# 11_EXPANSION_CN.net
KiCad netlist of a schematic drawn in Altium Designer
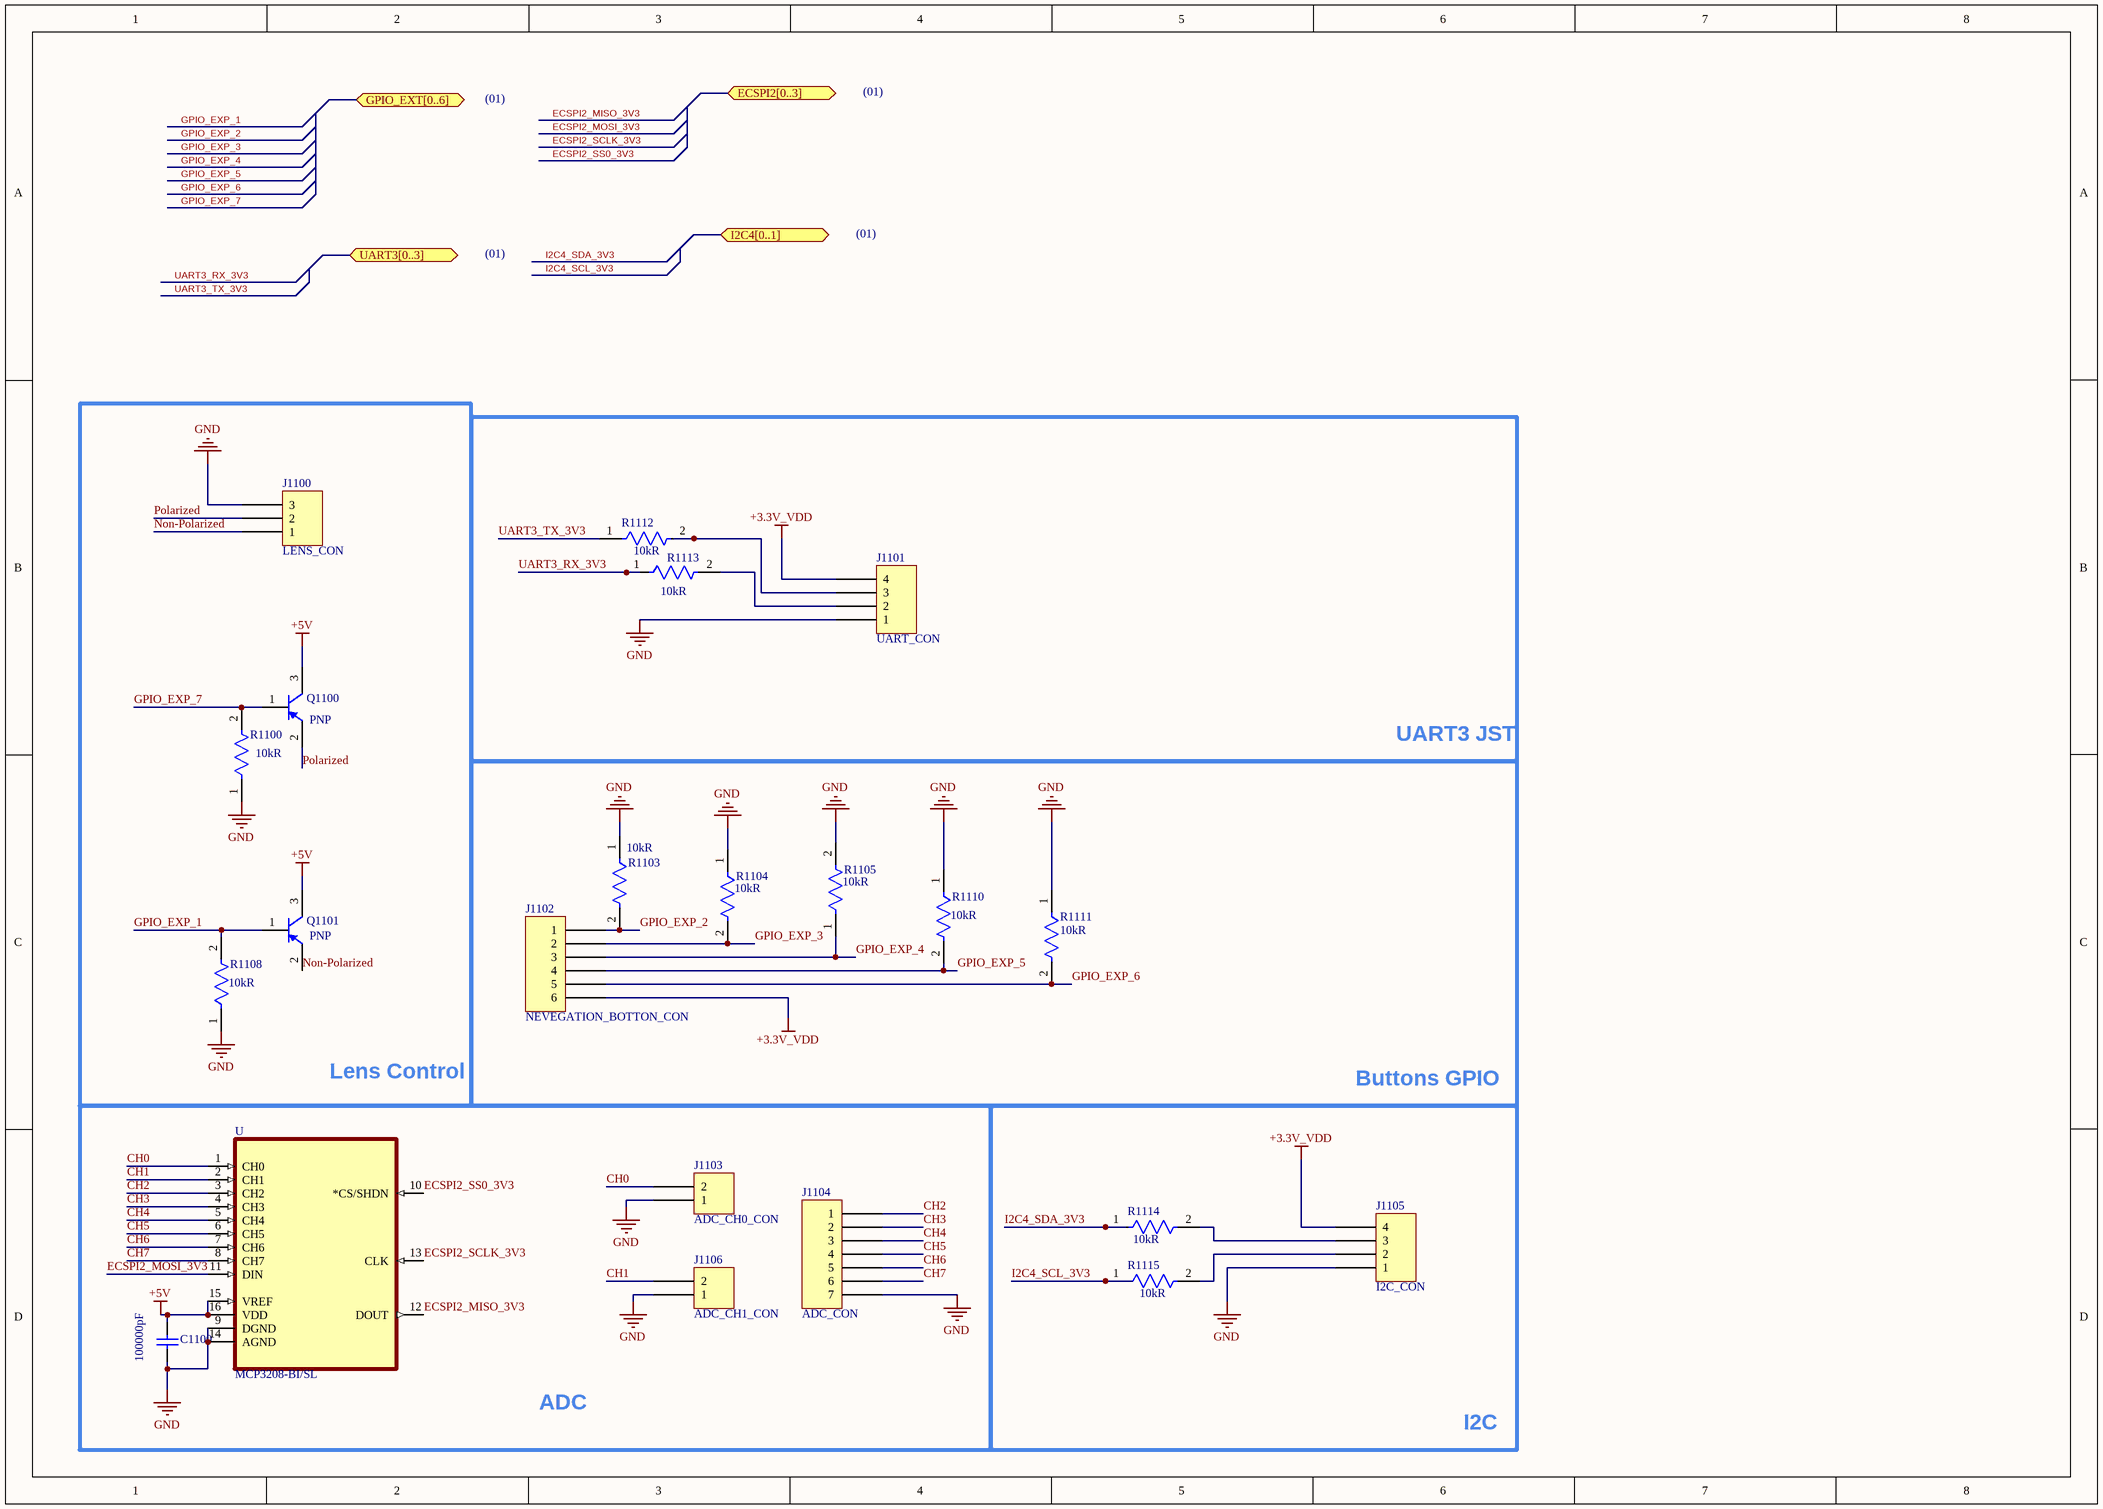
[diagram p0: 11 EXPANSION CN.SchDoc]

(export (version "E")
  (design (tool "Eeschema 10.0.6"))
  (components
    (comp (ref "C1100")
      (value "CL05B104KO5NNNC")
      (footprint "CAPC1050X55X23ML05T13")
      (description "Chip Capacitor, 100 nF, +/- 10%, 16 V, -55 to 125 degC, 0402 (1005 Metric), RoHS, Tape and Reel")
      (fields (field (name "CAPACITANCE") "100000pF"))
      (libsource (lib "Altium Content Vault") (part "CAP-NP-2"))
    )
    (comp (ref "J1100")
      (value "LENS_CON")
      (footprint "HIROSE DF13-3P-1.25H")
      (description "CONN HEADER SMD R/A 3POS 1.25MM")
      (fields
        (field (name "PART NUMBER") "DF13-3P-1.25H(75)")
        (field (name "MANUFACTURER") "Hirose Electric Co Ltd")
      )
      (libsource (lib "Celestial Altium Library - altium_library") (part "3 Pin"))
    )
    (comp (ref "J1101")
      (value "UART_CON")
      (footprint "HIROSE DF13A-4P-1.25H")
      (description "CONN HEADER SMD R/A 4POS 1.25MM")
      (fields
        (field (name "PART NUMBER") "DF13A-4P-1.25H(75)")
        (field (name "MANUFACTURER") "Hirose Electric Co Ltd")
      )
      (libsource (lib "Celestial Altium Library - altium_library") (part "4 Pin"))
    )
    (comp (ref "J1102")
      (value "NEVEGATION_BOTTON_CON")
      (footprint "HIROSE DF13A-6P-1.25H")
      (description "CONN HEADER SMD R/A 6POS 1.25MM")
      (fields
        (field (name "PART NUMBER") "DF13A-6P-1.25H(75)")
        (field (name "MANUFACTURER") "Hirose Electric Co Ltd")
      )
      (libsource (lib "Celestial Altium Library - altium_library") (part "6 Pin"))
    )
    (comp (ref "J1103")
      (value "ADC_CH0_CON")
      (footprint "HIROSE DF13-2P-1.25H")
      (description "CONN HEADER SMD R/A 2POS 1.25MM")
      (fields
        (field (name "PART NUMBER") "DF13-2P-1.25H(75)")
        (field (name "MANUFACTURER") "Hirose Electric Co Ltd")
      )
      (libsource (lib "Celestial Altium Library - altium_library") (part "2 Pin"))
    )
    (comp (ref "J1104")
      (value "ADC_CON")
      (footprint "JST SM07B-SRSS-TB")
      (description "CONN HEADER SMD R/A 7POS 1MM")
      (fields
        (field (name "PART NUMBER") "SM07B-SRSS-TB(LF)(SN)")
        (field (name "MANUFACTURER") "JST Sales America Inc.")
      )
      (libsource (lib "Celestial Altium Library - altium_library") (part "7 Pin"))
    )
    (comp (ref "J1105")
      (value "I2C_CON")
      (footprint "HIROSE DF13A-4P-1.25H")
      (description "CONN HEADER SMD R/A 4POS 1.25MM")
      (fields
        (field (name "PART NUMBER") "DF13A-4P-1.25H(75)")
        (field (name "MANUFACTURER") "Hirose Electric Co Ltd")
      )
      (libsource (lib "Celestial Altium Library - altium_library") (part "4 Pin"))
    )
    (comp (ref "J1106")
      (value "ADC_CH1_CON")
      (footprint "HIROSE DF13-2P-1.25H")
      (description "CONN HEADER SMD R/A 2POS 1.25MM")
      (fields
        (field (name "PART NUMBER") "DF13-2P-1.25H(75)")
        (field (name "MANUFACTURER") "Hirose Electric Co Ltd")
      )
      (libsource (lib "Celestial Altium Library - altium_library") (part "2 Pin"))
    )
    (comp (ref "Q1100")
      (value "BC807-40LT1G")
      (footprint "ONSC-SOT-23-3-318-08_V")
      (description "General Purpose Transistor, PNP Silicon, 3-Pin SOT-23, Pb-Free, Tape and Reel")
      (fields (field (name "POLARITY") "PNP"))
      (libsource (lib "Altium Content Vault") (part "ONSC-PNP-B1E2C3-3"))
    )
    (comp (ref "Q1101")
      (value "BC807-40LT1G")
      (footprint "ONSC-SOT-23-3-318-08_V")
      (description "General Purpose Transistor, PNP Silicon, 3-Pin SOT-23, Pb-Free, Tape and Reel")
      (fields (field (name "POLARITY") "PNP"))
      (libsource (lib "Altium Content Vault") (part "ONSC-PNP-B1E2C3-3"))
    )
    (comp (ref "R1100")
      (value "RMCF0603JT10K0")
      (footprint "FP-RMCF0603-IPC_C")
      (description "10kΩ ±5% 0.1W 0603 Thick Film Chip Resistor AEC-Q200 compliant")
      (fields (field (name "TOLERANCE") "5%") (field (name "RESISTANCE") "10kR"))
      (libsource (lib "Altium Content Vault") (part "1029c3af85768c4190bb7ad29bc67b5"))
    )
    (comp (ref "R1103")
      (value "RMCF0603JT10K0")
      (footprint "FP-RMCF0603-IPC_C")
      (description "10kΩ ±5% 0.1W 0603 Thick Film Chip Resistor AEC-Q200 compliant")
      (fields (field (name "TOLERANCE") "5%") (field (name "RESISTANCE") "10kR"))
      (libsource (lib "Altium Content Vault") (part "1029c3af85768c4190bb7ad29bc67b5"))
    )
    (comp (ref "R1104")
      (value "RMCF0603JT10K0")
      (footprint "FP-RMCF0603-IPC_C")
      (description "10kΩ ±5% 0.1W 0603 Thick Film Chip Resistor AEC-Q200 compliant")
      (fields (field (name "TOLERANCE") "5%") (field (name "RESISTANCE") "10kR"))
      (libsource (lib "Altium Content Vault") (part "1029c3af85768c4190bb7ad29bc67b5"))
    )
    (comp (ref "R1105")
      (value "RMCF0603JT10K0")
      (footprint "FP-RMCF0603-IPC_C")
      (description "10kΩ ±5% 0.1W 0603 Thick Film Chip Resistor AEC-Q200 compliant")
      (fields (field (name "TOLERANCE") "5%") (field (name "RESISTANCE") "10kR"))
      (libsource (lib "Altium Content Vault") (part "1029c3af85768c4190bb7ad29bc67b5"))
    )
    (comp (ref "R1108")
      (value "RMCF0603JT10K0")
      (footprint "FP-RMCF0603-IPC_C")
      (description "10kΩ ±5% 0.1W 0603 Thick Film Chip Resistor AEC-Q200 compliant")
      (fields (field (name "TOLERANCE") "5%") (field (name "RESISTANCE") "10kR"))
      (libsource (lib "Altium Content Vault") (part "1029c3af85768c4190bb7ad29bc67b5"))
    )
    (comp (ref "R1110")
      (value "RMCF0603JT10K0")
      (footprint "FP-RMCF0603-IPC_C")
      (description "10kΩ ±5% 0.1W 0603 Thick Film Chip Resistor AEC-Q200 compliant")
      (fields (field (name "TOLERANCE") "5%") (field (name "RESISTANCE") "10kR"))
      (libsource (lib "Altium Content Vault") (part "1029c3af85768c4190bb7ad29bc67b5"))
    )
    (comp (ref "R1111")
      (value "RMCF0603JT10K0")
      (footprint "FP-RMCF0603-IPC_C")
      (description "10kΩ ±5% 0.1W 0603 Thick Film Chip Resistor AEC-Q200 compliant")
      (fields (field (name "TOLERANCE") "5%") (field (name "RESISTANCE") "10kR"))
      (libsource (lib "Altium Content Vault") (part "1029c3af85768c4190bb7ad29bc67b5"))
    )
    (comp (ref "R1112")
      (value "RMCF0603JT10K0")
      (footprint "FP-RMCF0603-IPC_C")
      (description "10kΩ ±5% 0.1W 0603 Thick Film Chip Resistor AEC-Q200 compliant")
      (fields (field (name "TOLERANCE") "5%") (field (name "RESISTANCE") "10kR"))
      (libsource (lib "Altium Content Vault") (part "1029c3af85768c4190bb7ad29bc67b5"))
    )
    (comp (ref "R1113")
      (value "RMCF0603JT10K0")
      (footprint "FP-RMCF0603-IPC_C")
      (description "10kΩ ±5% 0.1W 0603 Thick Film Chip Resistor AEC-Q200 compliant")
      (fields (field (name "TOLERANCE") "5%") (field (name "RESISTANCE") "10kR"))
      (libsource (lib "Altium Content Vault") (part "1029c3af85768c4190bb7ad29bc67b5"))
    )
    (comp (ref "R1114")
      (value "RMCF0603JT10K0")
      (footprint "FP-RMCF0603-IPC_C")
      (description "10kΩ ±5% 0.1W 0603 Thick Film Chip Resistor AEC-Q200 compliant")
      (fields (field (name "TOLERANCE") "5%") (field (name "RESISTANCE") "10kR"))
      (libsource (lib "Altium Content Vault") (part "1029c3af85768c4190bb7ad29bc67b5"))
    )
    (comp (ref "R1115")
      (value "RMCF0603JT10K0")
      (footprint "FP-RMCF0603-IPC_C")
      (description "10kΩ ±5% 0.1W 0603 Thick Film Chip Resistor AEC-Q200 compliant")
      (fields (field (name "TOLERANCE") "5%") (field (name "RESISTANCE") "10kR"))
      (libsource (lib "Altium Content Vault") (part "1029c3af85768c4190bb7ad29bc67b5"))
    )
    (comp (ref "U")
      (value "MCP3208-BI/SL")
      (footprint "SOIC127P600X175-16N")
      (description "12 Bit Analog to Digital Converter 4, 8 Input 1 SAR 16-SOIC")
      (libsource (lib "MCP3208-BI_SL") (part "MCP3208-BI/SL"))
    )
  )
  (nets
    (net (code "18") (name "+3.3V_VDD") (class "Default")
      (node (ref "J1101") (pin "4") (pinfunction "4_4") (pintype "passive"))
      (node (ref "J1102") (pin "6") (pinfunction "6_6") (pintype "passive"))
      (node (ref "J1105") (pin "4") (pinfunction "4_4") (pintype "passive"))
    )
    (net (code "19") (name "+5V") (class "Default")
      (node (ref "C1100") (pin "2") (pinfunction "2_2") (pintype "passive"))
      (node (ref "Q1100") (pin "3") (pinfunction "C_3") (pintype "passive"))
      (node (ref "Q1101") (pin "3") (pinfunction "C_3") (pintype "passive"))
      (node (ref "U") (pin "15") (pinfunction "VREF_15") (pintype "input"))
      (node (ref "U") (pin "16") (pinfunction "VDD_16") (pintype "power_in"))
    )
    (net (code "20") (name "/CH0") (class "Default")
      (node (ref "J1103") (pin "2") (pinfunction "2_2") (pintype "passive"))
      (node (ref "U") (pin "1") (pinfunction "CH0_1") (pintype "input"))
    )
    (net (code "21") (name "/CH1") (class "Default")
      (node (ref "J1106") (pin "2") (pinfunction "2_2") (pintype "passive"))
      (node (ref "U") (pin "2") (pinfunction "CH1_2") (pintype "input"))
    )
    (net (code "22") (name "/CH2") (class "Default")
      (node (ref "J1104") (pin "1") (pinfunction "1_1") (pintype "passive"))
      (node (ref "U") (pin "3") (pinfunction "CH2_3") (pintype "input"))
    )
    (net (code "23") (name "/CH3") (class "Default")
      (node (ref "J1104") (pin "2") (pinfunction "2_2") (pintype "passive"))
      (node (ref "U") (pin "4") (pinfunction "CH3_4") (pintype "input"))
    )
    (net (code "24") (name "/CH4") (class "Default")
      (node (ref "J1104") (pin "3") (pinfunction "3_3") (pintype "passive"))
      (node (ref "U") (pin "5") (pinfunction "CH4_5") (pintype "input"))
    )
    (net (code "25") (name "/CH5") (class "Default")
      (node (ref "J1104") (pin "4") (pinfunction "4_4") (pintype "passive"))
      (node (ref "U") (pin "6") (pinfunction "CH5_6") (pintype "input"))
    )
    (net (code "26") (name "/CH6") (class "Default")
      (node (ref "J1104") (pin "5") (pinfunction "5_5") (pintype "passive"))
      (node (ref "U") (pin "7") (pinfunction "CH6_7") (pintype "input"))
    )
    (net (code "27") (name "/CH7") (class "Default")
      (node (ref "J1104") (pin "6") (pinfunction "6_6") (pintype "passive"))
      (node (ref "U") (pin "8") (pinfunction "CH7_8") (pintype "input"))
    )
    (net (code "29") (name "/ECSPI2_MISO_3V3") (class "Default")
      (node (ref "U") (pin "12") (pinfunction "DOUT_12") (pintype "output"))
    )
    (net (code "30") (name "/ECSPI2_MOSI_3V3") (class "Default")
      (node (ref "U") (pin "11") (pinfunction "DIN_11") (pintype "input"))
    )
    (net (code "31") (name "/ECSPI2_SCLK_3V3") (class "Default")
      (node (ref "U") (pin "13") (pinfunction "CLK_13") (pintype "input"))
    )
    (net (code "32") (name "/ECSPI2_SS0_3V3") (class "Default")
      (node (ref "U") (pin "10") (pinfunction "*CS/SHDN_10") (pintype "input"))
    )
    (net (code "33") (name "/GPIO_EXP_1") (class "Default")
      (node (ref "Q1101") (pin "1") (pinfunction "B_1") (pintype "passive"))
      (node (ref "R1108") (pin "2") (pinfunction "2_2") (pintype "passive"))
    )
    (net (code "34") (name "/GPIO_EXP_2") (class "Default")
      (node (ref "J1102") (pin "1") (pinfunction "1_1") (pintype "passive"))
      (node (ref "R1103") (pin "2") (pinfunction "2_2") (pintype "passive"))
    )
    (net (code "35") (name "/GPIO_EXP_3") (class "Default")
      (node (ref "J1102") (pin "2") (pinfunction "2_2") (pintype "passive"))
      (node (ref "R1104") (pin "2") (pinfunction "2_2") (pintype "passive"))
    )
    (net (code "36") (name "/GPIO_EXP_4") (class "Default")
      (node (ref "J1102") (pin "3") (pinfunction "3_3") (pintype "passive"))
      (node (ref "R1105") (pin "1") (pinfunction "1_1") (pintype "passive"))
    )
    (net (code "37") (name "/GPIO_EXP_5") (class "Default")
      (node (ref "J1102") (pin "4") (pinfunction "4_4") (pintype "passive"))
      (node (ref "R1110") (pin "2") (pinfunction "2_2") (pintype "passive"))
    )
    (net (code "38") (name "/GPIO_EXP_6") (class "Default")
      (node (ref "J1102") (pin "5") (pinfunction "5_5") (pintype "passive"))
      (node (ref "R1111") (pin "2") (pinfunction "2_2") (pintype "passive"))
    )
    (net (code "39") (name "/GPIO_EXP_7") (class "Default")
      (node (ref "Q1100") (pin "1") (pinfunction "B_1") (pintype "passive"))
      (node (ref "R1100") (pin "2") (pinfunction "2_2") (pintype "passive"))
    )
    (net (code "42") (name "/I2C4_SCL_3V3") (class "Default")
      (node (ref "R1115") (pin "1") (pinfunction "1_1") (pintype "passive"))
    )
    (net (code "43") (name "/I2C4_SDA_3V3") (class "Default")
      (node (ref "R1114") (pin "1") (pinfunction "1_1") (pintype "passive"))
    )
    (net (code "44") (name "/Non-Polarized") (class "Default")
      (node (ref "J1100") (pin "1") (pinfunction "1_1") (pintype "passive"))
      (node (ref "Q1101") (pin "2") (pinfunction "E_2") (pintype "passive"))
    )
    (net (code "45") (name "/Polarized") (class "Default")
      (node (ref "J1100") (pin "2") (pinfunction "2_2") (pintype "passive"))
      (node (ref "Q1100") (pin "2") (pinfunction "E_2") (pintype "passive"))
    )
    (net (code "47") (name "/UART3_RX_3V3") (class "Default")
      (node (ref "R1113") (pin "1") (pinfunction "1_1") (pintype "passive"))
    )
    (net (code "48") (name "/UART3_TX_3V3") (class "Default")
      (node (ref "R1112") (pin "1") (pinfunction "1_1") (pintype "passive"))
    )
    (net (code "49") (name "GND") (class "Default")
      (node (ref "C1100") (pin "1") (pinfunction "1_1") (pintype "passive"))
      (node (ref "J1100") (pin "3") (pinfunction "3_3") (pintype "passive"))
      (node (ref "J1101") (pin "1") (pinfunction "1_1") (pintype "passive"))
      (node (ref "J1103") (pin "1") (pinfunction "1_1") (pintype "passive"))
      (node (ref "J1104") (pin "7") (pinfunction "7_7") (pintype "passive"))
      (node (ref "J1105") (pin "1") (pinfunction "1_1") (pintype "passive"))
      (node (ref "J1106") (pin "1") (pinfunction "1_1") (pintype "passive"))
      (node (ref "R1100") (pin "1") (pinfunction "1_1") (pintype "passive"))
      (node (ref "R1103") (pin "1") (pinfunction "1_1") (pintype "passive"))
      (node (ref "R1104") (pin "1") (pinfunction "1_1") (pintype "passive"))
      (node (ref "R1105") (pin "2") (pinfunction "2_2") (pintype "passive"))
      (node (ref "R1108") (pin "1") (pinfunction "1_1") (pintype "passive"))
      (node (ref "R1110") (pin "1") (pinfunction "1_1") (pintype "passive"))
      (node (ref "R1111") (pin "1") (pinfunction "1_1") (pintype "passive"))
      (node (ref "U") (pin "14") (pinfunction "AGND_14") (pintype "passive"))
      (node (ref "U") (pin "9") (pinfunction "DGND_9") (pintype "passive"))
    )
    (net (code "50") (name "Net-(J1101-Pad2)") (class "Default")
      (node (ref "J1101") (pin "2") (pinfunction "2_2") (pintype "passive"))
      (node (ref "R1113") (pin "2") (pinfunction "2_2") (pintype "passive"))
    )
    (net (code "51") (name "Net-(J1101-Pad3)") (class "Default")
      (node (ref "J1101") (pin "3") (pinfunction "3_3") (pintype "passive"))
      (node (ref "R1112") (pin "2") (pinfunction "2_2") (pintype "passive"))
    )
    (net (code "52") (name "Net-(J1105-Pad2)") (class "Default")
      (node (ref "J1105") (pin "2") (pinfunction "2_2") (pintype "passive"))
      (node (ref "R1115") (pin "2") (pinfunction "2_2") (pintype "passive"))
    )
    (net (code "53") (name "Net-(J1105-Pad3)") (class "Default")
      (node (ref "J1105") (pin "3") (pinfunction "3_3") (pintype "passive"))
      (node (ref "R1114") (pin "2") (pinfunction "2_2") (pintype "passive"))
    )
  )
)
